# MCP39F511A.net
KiCad netlist of a schematic drawn in Altium Designer
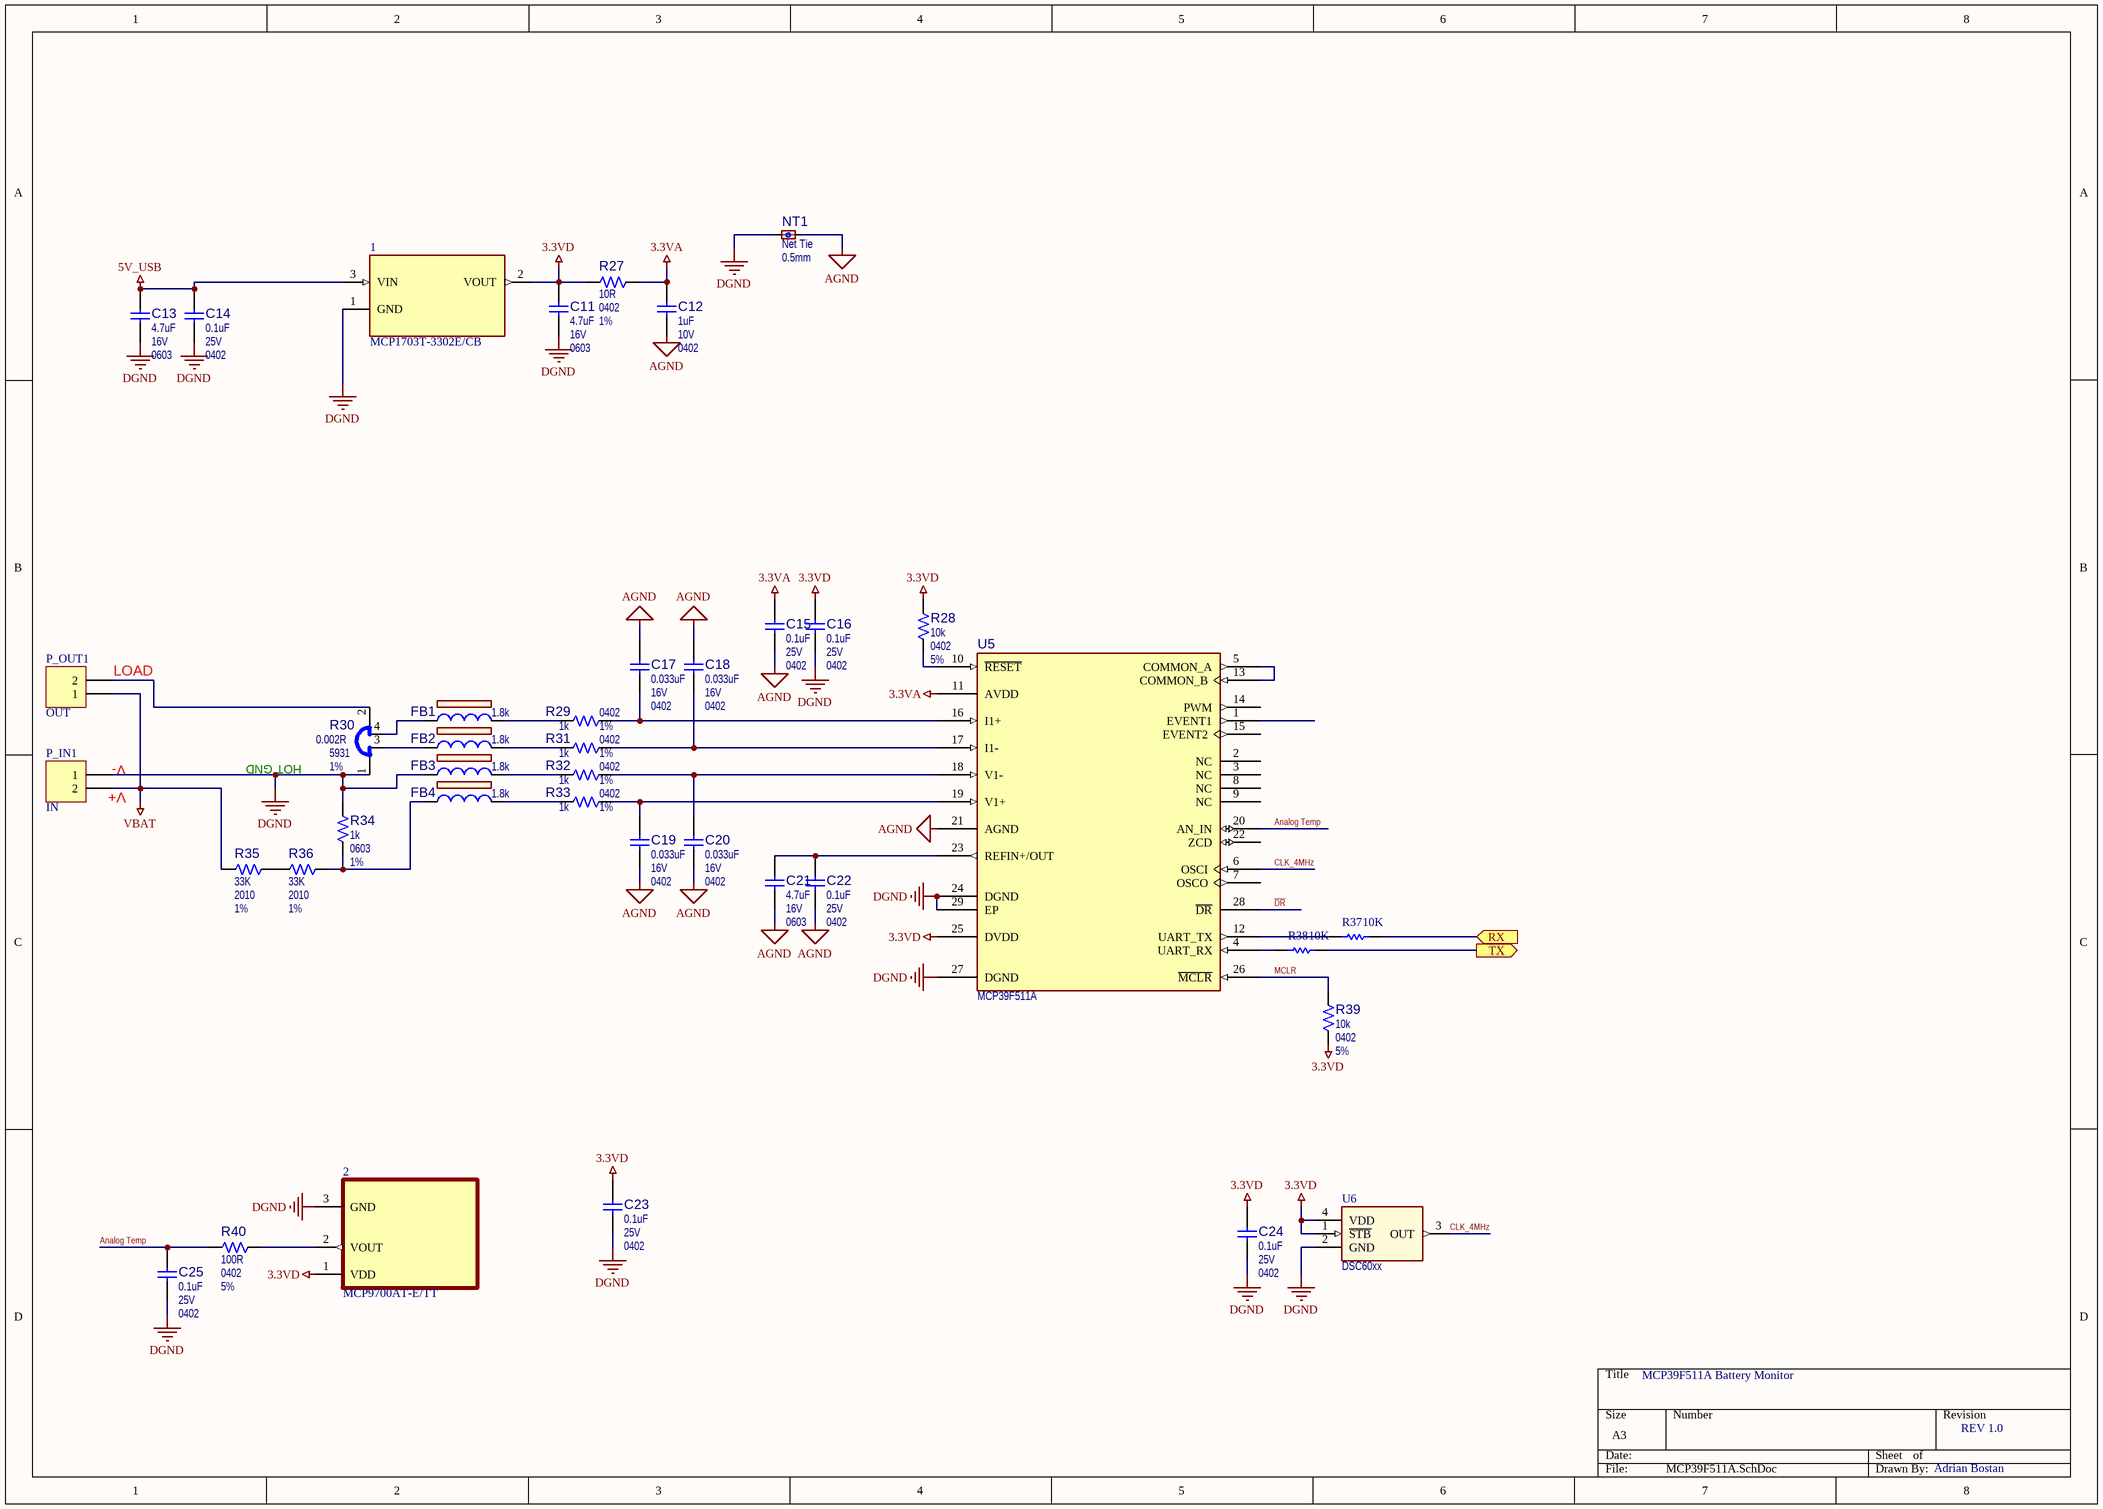
[diagram p0: MCP39F511A.SchDoc]

(export (version "E")
  (design (tool "Eeschema 10.0.6"))
  (components
    (comp (ref "1")
      (value "MCP1703T-3302E/CB")
      (footprint "SOT95P300X145-3N")
      (description "Linear Voltage Regulator IC 1 Output 250mA SOT-23A-3")
      (fields (field (name "MF") "Microchip"))
      (libsource (lib "MCP1703T-3302E_CB") (part "MCP1703T-3302E/CB"))
    )
    (comp (ref "2")
      (value "MCP9700AT-E/TT")
      (footprint "SOT95P237X112-3N")
      (description "Temperature Sensor Analog, Local -40Â°C ~ 125Â°C 10mV/Â°C SOT-23-3")
      (fields (field (name "MF") "Microchip"))
      (libsource (lib "MCP9700AT-E_TT") (part "MCP9700AT-E/TT"))
    )
    (comp (ref "C11")
      (value "4.7uF")
      (footprint "CAP0603M")
      (description "Capacitor")
      (fields
        (field (name "VOLTAGE") "16V")
        (field (name "PACKAGE") "0603")
        (field (name "TOLERANCE") "10%")
        (field (name "OWNER") "Jairuz Agang-ang")
      )
      (libsource (lib "MCHP-CDB") (part "Capacitor NP"))
    )
    (comp (ref "C12")
      (value "1uF")
      (footprint "CAP0603M")
      (description "Capacitor")
      (fields
        (field (name "VOLTAGE") "10V")
        (field (name "PACKAGE") "0402")
        (field (name "TOLERANCE") "10%")
        (field (name "OWNER") "Aaron VanDuerm")
      )
      (libsource (lib "MCHP-CDB") (part "Capacitor NP"))
    )
    (comp (ref "C13")
      (value "4.7uF")
      (footprint "CAP0603M")
      (description "Capacitor")
      (fields
        (field (name "VOLTAGE") "16V")
        (field (name "PACKAGE") "0603")
        (field (name "TOLERANCE") "10%")
        (field (name "OWNER") "Jairuz Agang-ang")
      )
      (libsource (lib "MCHP-CDB") (part "Capacitor NP"))
    )
    (comp (ref "C14")
      (value "0.1uF")
      (footprint "CAP0603M")
      (description "Capacitor")
      (fields
        (field (name "VOLTAGE") "25V")
        (field (name "PACKAGE") "0402")
        (field (name "TOLERANCE") "10%")
        (field (name "OWNER") "Randolph Sobrepena")
      )
      (libsource (lib "MCHP-CDB") (part "Capacitor NP"))
    )
    (comp (ref "C15")
      (value "0.1uF")
      (footprint "CAP0603M")
      (description "Capacitor")
      (fields
        (field (name "VOLTAGE") "25V")
        (field (name "PACKAGE") "0402")
        (field (name "TOLERANCE") "10%")
        (field (name "OWNER") "Randolph Sobrepena")
      )
      (libsource (lib "MCHP-CDB") (part "Capacitor NP"))
    )
    (comp (ref "C16")
      (value "0.1uF")
      (footprint "CAP0603M")
      (description "Capacitor")
      (fields
        (field (name "VOLTAGE") "25V")
        (field (name "PACKAGE") "0402")
        (field (name "TOLERANCE") "10%")
        (field (name "OWNER") "Randolph Sobrepena")
      )
      (libsource (lib "MCHP-CDB") (part "Capacitor NP"))
    )
    (comp (ref "C17")
      (value "0.033uF")
      (footprint "CAP0603M")
      (description "Capacitor")
      (fields
        (field (name "VOLTAGE") "16V")
        (field (name "PACKAGE") "0402")
        (field (name "TOLERANCE") "10%")
        (field (name "OWNER") "Bogdan Popescu")
      )
      (libsource (lib "MCHP-CDB") (part "Capacitor NP"))
    )
    (comp (ref "C18")
      (value "0.033uF")
      (footprint "CAP0603M")
      (description "Capacitor")
      (fields
        (field (name "VOLTAGE") "16V")
        (field (name "PACKAGE") "0402")
        (field (name "TOLERANCE") "10%")
        (field (name "OWNER") "Bogdan Popescu")
      )
      (libsource (lib "MCHP-CDB") (part "Capacitor NP"))
    )
    (comp (ref "C19")
      (value "0.033uF")
      (footprint "CAP0603M")
      (description "Capacitor")
      (fields
        (field (name "VOLTAGE") "16V")
        (field (name "PACKAGE") "0402")
        (field (name "TOLERANCE") "10%")
        (field (name "OWNER") "Bogdan Popescu")
      )
      (libsource (lib "MCHP-CDB") (part "Capacitor NP"))
    )
    (comp (ref "C20")
      (value "0.033uF")
      (footprint "CAP0603M")
      (description "Capacitor")
      (fields
        (field (name "VOLTAGE") "16V")
        (field (name "PACKAGE") "0402")
        (field (name "TOLERANCE") "10%")
        (field (name "OWNER") "Bogdan Popescu")
      )
      (libsource (lib "MCHP-CDB") (part "Capacitor NP"))
    )
    (comp (ref "C21")
      (value "4.7uF")
      (footprint "CAP0603M")
      (description "Capacitor")
      (fields
        (field (name "VOLTAGE") "16V")
        (field (name "PACKAGE") "0603")
        (field (name "TOLERANCE") "10%")
        (field (name "OWNER") "Jairuz Agang-ang")
      )
      (libsource (lib "MCHP-CDB") (part "Capacitor NP"))
    )
    (comp (ref "C22")
      (value "0.1uF")
      (footprint "CAP0603M")
      (description "Capacitor")
      (fields
        (field (name "VOLTAGE") "25V")
        (field (name "PACKAGE") "0402")
        (field (name "TOLERANCE") "10%")
        (field (name "OWNER") "Randolph Sobrepena")
      )
      (libsource (lib "MCHP-CDB") (part "Capacitor NP"))
    )
    (comp (ref "C23")
      (value "0.1uF")
      (footprint "CAP0603M")
      (description "Capacitor")
      (fields
        (field (name "VOLTAGE") "25V")
        (field (name "PACKAGE") "0402")
        (field (name "TOLERANCE") "10%")
        (field (name "OWNER") "Randolph Sobrepena")
      )
      (libsource (lib "MCHP-CDB") (part "Capacitor NP"))
    )
    (comp (ref "C24")
      (value "0.1uF")
      (footprint "CAP0603M")
      (description "Capacitor")
      (fields
        (field (name "VOLTAGE") "25V")
        (field (name "PACKAGE") "0402")
        (field (name "TOLERANCE") "10%")
        (field (name "OWNER") "Randolph Sobrepena")
      )
      (libsource (lib "MCHP-CDB") (part "Capacitor NP"))
    )
    (comp (ref "C25")
      (value "0.1uF")
      (footprint "CAP0603M")
      (description "Capacitor")
      (fields
        (field (name "VOLTAGE") "25V")
        (field (name "PACKAGE") "0402")
        (field (name "TOLERANCE") "10%")
        (field (name "OWNER") "Randolph Sobrepena")
      )
      (libsource (lib "MCHP-CDB") (part "Capacitor NP"))
    )
    (comp (ref "FB1")
      (value "1.8k")
      (footprint "RES0603M")
      (fields (field (name "OWNER") "Razvan Cristescu"))
      (libsource (lib "MCHP-CDB") (part "Ferrite Bead"))
    )
    (comp (ref "FB2")
      (value "1.8k")
      (footprint "RES0603M")
      (fields (field (name "OWNER") "Razvan Cristescu"))
      (libsource (lib "MCHP-CDB") (part "Ferrite Bead"))
    )
    (comp (ref "FB3")
      (value "1.8k")
      (footprint "RES0603M")
      (fields (field (name "OWNER") "Razvan Cristescu"))
      (libsource (lib "MCHP-CDB") (part "Ferrite Bead"))
    )
    (comp (ref "FB4")
      (value "1.8k")
      (footprint "RES0603M")
      (fields (field (name "OWNER") "Razvan Cristescu"))
      (libsource (lib "MCHP-CDB") (part "Ferrite Bead"))
    )
    (comp (ref "NT1")
      (value "Net Tie")
      (footprint "NET_TIE_0.5mm")
      (fields (field (name "PACKAGE") "0.5mm") (field (name "OWNER") "Bogdan P (M91398)"))
      (libsource (lib "MCHP-CDB") (part "Net Tie"))
    )
    (comp (ref "P_IN1")
      (value "IN")
      (footprint "XT60PW-M")
      (description "Header, 2-Pin")
      (fields (field (name "PUBLISHER") "Altium Limited"))
      (libsource (lib "Miscellaneous Connectors") (part "Header 2"))
    )
    (comp (ref "P_OUT1")
      (value "OUT")
      (footprint "XT60PW-F")
      (description "Header, 2-Pin")
      (fields (field (name "PUBLISHER") "Altium Limited"))
      (libsource (lib "") (part "Header 2_1"))
    )
    (comp (ref "R27")
      (value "10R")
      (footprint "RES0603M")
      (description "Resistor")
      (fields
        (field (name "PACKAGE") "0402")
        (field (name "TOLERANCE") "1%")
        (field (name "VOLTAGE") "50V")
        (field (name "POWER") "1/16W")
        (field (name "OWNER") "Tad Ahlvers")
      )
      (libsource (lib "MCHP-CDB") (part "Resistor"))
    )
    (comp (ref "R28")
      (value "10k")
      (footprint "RES0603M")
      (description "Resistor")
      (fields
        (field (name "PACKAGE") "0402")
        (field (name "TOLERANCE") "5%")
        (field (name "VOLTAGE") "50V")
        (field (name "POWER") "1/16W")
      )
      (libsource (lib "MCHP-CDB") (part "Resistor"))
    )
    (comp (ref "R29")
      (value "1k")
      (footprint "RES0603M")
      (description "Resistor")
      (fields
        (field (name "PACKAGE") "0402")
        (field (name "TOLERANCE") "1%")
        (field (name "VOLTAGE") "50V")
        (field (name "POWER") "1/10W")
        (field (name "OWNER") "Tad Ahlvers")
      )
      (libsource (lib "MCHP-CDB") (part "Resistor"))
    )
    (comp (ref "R30")
      (value "0.002R")
      (footprint "5931")
      (description "Shunt")
      (fields
        (field (name "PACKAGE") "5931")
        (field (name "TOLERANCE") "1%")
        (field (name "VOLTAGE") "200V")
        (field (name "POWER") "2W")
        (field (name "OWNER") "Bogdan P (M91398)")
      )
      (libsource (lib "MCHP-CDB") (part "Shunt 4 Pin"))
    )
    (comp (ref "R31")
      (value "1k")
      (footprint "RES0603M")
      (description "Resistor")
      (fields
        (field (name "PACKAGE") "0402")
        (field (name "TOLERANCE") "1%")
        (field (name "VOLTAGE") "50V")
        (field (name "POWER") "1/10W")
        (field (name "OWNER") "Tad Ahlvers")
      )
      (libsource (lib "MCHP-CDB") (part "Resistor"))
    )
    (comp (ref "R32")
      (value "1k")
      (footprint "RES0603M")
      (description "Resistor")
      (fields
        (field (name "PACKAGE") "0402")
        (field (name "TOLERANCE") "1%")
        (field (name "VOLTAGE") "50V")
        (field (name "POWER") "1/10W")
        (field (name "OWNER") "Tad Ahlvers")
      )
      (libsource (lib "MCHP-CDB") (part "Resistor"))
    )
    (comp (ref "R33")
      (value "1k")
      (footprint "RES0603M")
      (description "Resistor")
      (fields
        (field (name "PACKAGE") "0402")
        (field (name "TOLERANCE") "1%")
        (field (name "VOLTAGE") "50V")
        (field (name "POWER") "1/10W")
        (field (name "OWNER") "Tad Ahlvers")
      )
      (libsource (lib "MCHP-CDB") (part "Resistor"))
    )
    (comp (ref "R34")
      (value "1k")
      (footprint "RES0603M")
      (description "Resistor")
      (fields
        (field (name "PACKAGE") "0603")
        (field (name "TOLERANCE") "1%")
        (field (name "VOLTAGE") "75V")
        (field (name "POWER") "1/10W")
      )
      (libsource (lib "MCHP-CDB") (part "Resistor"))
    )
    (comp (ref "R35")
      (value "33K")
      (footprint "RES2010")
      (description "Resistor")
      (fields
        (field (name "PACKAGE") "2010")
        (field (name "TOLERANCE") "1%")
        (field (name "VOLTAGE") "400V")
        (field (name "POWER") "3/4W")
        (field (name "OWNER") "Bogdan Popescu")
      )
      (libsource (lib "MCHP-CDB") (part "Resistor"))
    )
    (comp (ref "R36")
      (value "33K")
      (footprint "RES2010")
      (description "Resistor")
      (fields
        (field (name "PACKAGE") "2010")
        (field (name "TOLERANCE") "1%")
        (field (name "VOLTAGE") "400V")
        (field (name "POWER") "3/4W")
        (field (name "OWNER") "Bogdan Popescu")
      )
      (libsource (lib "MCHP-CDB") (part "Resistor"))
    )
    (comp (ref "R37")
      (value "10K")
      (footprint "RES0603M")
      (description "Resistor")
      (fields (field (name "Comment") "Res1") (field (name "PUBLISHER") "Altium Limited"))
      (libsource (lib "Miscellaneous Devices") (part "Res1"))
    )
    (comp (ref "R38")
      (value "10K")
      (footprint "RES0603M")
      (description "Resistor")
      (fields (field (name "Comment") "Res1") (field (name "PUBLISHER") "Altium Limited"))
      (libsource (lib "Miscellaneous Devices") (part "Res1"))
    )
    (comp (ref "R39")
      (value "10k")
      (footprint "RES0603M")
      (description "Resistor")
      (fields
        (field (name "PACKAGE") "0402")
        (field (name "TOLERANCE") "5%")
        (field (name "VOLTAGE") "50V")
        (field (name "POWER") "1/16W")
      )
      (libsource (lib "MCHP-CDB") (part "Resistor"))
    )
    (comp (ref "R40")
      (value "100R")
      (footprint "RES0603M")
      (description "Resistor")
      (fields
        (field (name "PACKAGE") "0402")
        (field (name "TOLERANCE") "5%")
        (field (name "VOLTAGE") "50V")
        (field (name "POWER") "1/16W")
        (field (name "OWNER") "Sompoch Loboonlert")
      )
      (libsource (lib "MCHP-CDB") (part "Resistor"))
    )
    (comp (ref "U5")
      (value "MCP39F511A")
      (footprint "QFN50P500X500X100-29N")
      (description "ADC")
      (fields (field (name "Comment") "MCP39F511 QFN-28") (field (name "OWNER") "Bogdan Popescu"))
      (libsource (lib "MCHP-CDB") (part "MCP39F511 QFN-28"))
    )
    (comp (ref "U6")
      (value "DSC60xx")
      (footprint "DSC60xx")
      (fields (field (name "Comment") "OSCILLATOR DSC1001") (field (name "OWNER") "Tim Moffat"))
      (libsource (lib "MCHP-CDB") (part "OSCILLATOR DSC1001"))
    )
  )
  (nets
    (net (code "1") (name "/Analog Temp") (class "Default")
      (node (ref "C25") (pin "2") (pinfunction "2_2") (pintype "passive"))
      (node (ref "R40") (pin "1") (pinfunction "1_1") (pintype "passive"))
      (node (ref "U5") (pin "20") (pinfunction "AN_IN_20") (pintype "bidirectional"))
    )
    (net (code "2") (name "/CLK_4MHz") (class "Default")
      (node (ref "U5") (pin "6") (pinfunction "OSCI_6") (pintype "input"))
      (node (ref "U6") (pin "3") (pinfunction "OUT_3") (pintype "output"))
    )
    (net (code "3") (name "/MCLR") (class "Default")
      (node (ref "R39") (pin "2") (pinfunction "2_2") (pintype "passive"))
      (node (ref "U5") (pin "26") (pinfunction "~{MCLR}_26") (pintype "input"))
    )
    (net (code "4") (name "/RX") (class "Default")
      (node (ref "R37") (pin "1") (pinfunction "1_1") (pintype "passive"))
    )
    (net (code "5") (name "/TX") (class "Default")
      (node (ref "R38") (pin "1") (pinfunction "1_1") (pintype "passive"))
    )
    (net (code "6") (name "/~{DR}") (class "Default")
      (node (ref "U5") (pin "28") (pinfunction "~{DR}_28") (pintype "tri_state"))
    )
    (net (code "7") (name "3.3VA") (class "Default")
      (node (ref "C12") (pin "2") (pinfunction "2_2") (pintype "passive"))
      (node (ref "C15") (pin "2") (pinfunction "2_2") (pintype "passive"))
      (node (ref "R27") (pin "2") (pinfunction "2_2") (pintype "passive"))
      (node (ref "U5") (pin "11") (pinfunction "AVDD_11") (pintype "power_in"))
    )
    (net (code "8") (name "3.3VD") (class "Default")
      (node (ref "1") (pin "2") (pinfunction "VOUT_2") (pintype "output"))
      (node (ref "2") (pin "1") (pinfunction "VDD_1") (pintype "power_in"))
      (node (ref "C11") (pin "2") (pinfunction "2_2") (pintype "passive"))
      (node (ref "C16") (pin "2") (pinfunction "2_2") (pintype "passive"))
      (node (ref "C23") (pin "2") (pinfunction "2_2") (pintype "passive"))
      (node (ref "C24") (pin "2") (pinfunction "2_2") (pintype "passive"))
      (node (ref "R27") (pin "1") (pinfunction "1_1") (pintype "passive"))
      (node (ref "R28") (pin "2") (pinfunction "2_2") (pintype "passive"))
      (node (ref "R39") (pin "1") (pinfunction "1_1") (pintype "passive"))
      (node (ref "U5") (pin "25") (pinfunction "DVDD_25") (pintype "power_in"))
      (node (ref "U6") (pin "1") (pinfunction "~{STB}_1") (pintype "input"))
      (node (ref "U6") (pin "4") (pinfunction "VDD_4") (pintype "power_in"))
    )
    (net (code "9") (name "5V_USB") (class "Default")
      (node (ref "1") (pin "3") (pinfunction "VIN_3") (pintype "input"))
      (node (ref "C13") (pin "1") (pinfunction "1_1") (pintype "passive"))
      (node (ref "C14") (pin "2") (pinfunction "2_2") (pintype "passive"))
    )
    (net (code "10") (name "AGND") (class "Default")
      (node (ref "C12") (pin "1") (pinfunction "1_1") (pintype "passive"))
      (node (ref "C15") (pin "1") (pinfunction "1_1") (pintype "passive"))
      (node (ref "C17") (pin "2") (pinfunction "2_2") (pintype "passive"))
      (node (ref "C18") (pin "2") (pinfunction "2_2") (pintype "passive"))
      (node (ref "C19") (pin "1") (pinfunction "1_1") (pintype "passive"))
      (node (ref "C20") (pin "1") (pinfunction "1_1") (pintype "passive"))
      (node (ref "C21") (pin "1") (pinfunction "1_1") (pintype "passive"))
      (node (ref "C22") (pin "1") (pinfunction "1_1") (pintype "passive"))
      (node (ref "NT1") (pin "2") (pinfunction "2_2") (pintype "passive"))
      (node (ref "U5") (pin "21") (pinfunction "AGND_21") (pintype "power_in"))
    )
    (net (code "11") (name "DGND") (class "Default")
      (node (ref "1") (pin "1") (pinfunction "GND_1") (pintype "passive"))
      (node (ref "2") (pin "3") (pinfunction "GND_3") (pintype "power_in"))
      (node (ref "C11") (pin "1") (pinfunction "1_1") (pintype "passive"))
      (node (ref "C13") (pin "2") (pinfunction "2_2") (pintype "passive"))
      (node (ref "C14") (pin "1") (pinfunction "1_1") (pintype "passive"))
      (node (ref "C16") (pin "1") (pinfunction "1_1") (pintype "passive"))
      (node (ref "C23") (pin "1") (pinfunction "1_1") (pintype "passive"))
      (node (ref "C24") (pin "1") (pinfunction "1_1") (pintype "passive"))
      (node (ref "C25") (pin "1") (pinfunction "1_1") (pintype "passive"))
      (node (ref "FB3") (pin "1") (pinfunction "1_1") (pintype "passive"))
      (node (ref "NT1") (pin "1") (pinfunction "1_1") (pintype "passive"))
      (node (ref "P_IN1") (pin "1") (pinfunction "1_1") (pintype "passive"))
      (node (ref "R30") (pin "1") (pinfunction "1_1") (pintype "passive"))
      (node (ref "R34") (pin "2") (pinfunction "2_2") (pintype "passive"))
      (node (ref "U5") (pin "24") (pinfunction "DGND_24") (pintype "power_in"))
      (node (ref "U5") (pin "27") (pinfunction "DGND_27") (pintype "power_in"))
      (node (ref "U5") (pin "29") (pinfunction "EP_29") (pintype "passive"))
      (node (ref "U6") (pin "2") (pinfunction "GND_2") (pintype "power_in"))
    )
    (net (code "12") (name "Net-(2-VOUT)") (class "Default")
      (node (ref "2") (pin "2") (pinfunction "VOUT_2") (pintype "output"))
      (node (ref "R40") (pin "2") (pinfunction "2_2") (pintype "passive"))
    )
    (net (code "13") (name "Net-(FB1-Pad1)") (class "Default")
      (node (ref "FB1") (pin "1") (pinfunction "1_1") (pintype "passive"))
      (node (ref "R30") (pin "4") (pinfunction "4_4") (pintype "passive"))
    )
    (net (code "14") (name "Net-(FB1-Pad2)") (class "Default")
      (node (ref "FB1") (pin "2") (pinfunction "2_2") (pintype "passive"))
      (node (ref "R29") (pin "1") (pinfunction "1_1") (pintype "passive"))
    )
    (net (code "15") (name "Net-(FB2-Pad1)") (class "Default")
      (node (ref "FB2") (pin "1") (pinfunction "1_1") (pintype "passive"))
      (node (ref "R30") (pin "3") (pinfunction "3_3") (pintype "passive"))
    )
    (net (code "16") (name "Net-(FB2-Pad2)") (class "Default")
      (node (ref "FB2") (pin "2") (pinfunction "2_2") (pintype "passive"))
      (node (ref "R31") (pin "1") (pinfunction "1_1") (pintype "passive"))
    )
    (net (code "17") (name "Net-(FB3-Pad2)") (class "Default")
      (node (ref "FB3") (pin "2") (pinfunction "2_2") (pintype "passive"))
      (node (ref "R32") (pin "1") (pinfunction "1_1") (pintype "passive"))
    )
    (net (code "18") (name "Net-(FB4-Pad1)") (class "Default")
      (node (ref "FB4") (pin "1") (pinfunction "1_1") (pintype "passive"))
      (node (ref "R34") (pin "1") (pinfunction "1_1") (pintype "passive"))
      (node (ref "R36") (pin "1") (pinfunction "1_1") (pintype "passive"))
    )
    (net (code "19") (name "Net-(FB4-Pad2)") (class "Default")
      (node (ref "FB4") (pin "2") (pinfunction "2_2") (pintype "passive"))
      (node (ref "R33") (pin "1") (pinfunction "1_1") (pintype "passive"))
    )
    (net (code "20") (name "Net-(P_OUT1-Pad2)") (class "Default")
      (node (ref "P_OUT1") (pin "2") (pinfunction "2_2") (pintype "passive"))
      (node (ref "R30") (pin "2") (pinfunction "2_2") (pintype "passive"))
    )
    (net (code "21") (name "Net-(R35-Pad2)") (class "Default")
      (node (ref "R35") (pin "2") (pinfunction "2_2") (pintype "passive"))
      (node (ref "R36") (pin "2") (pinfunction "2_2") (pintype "passive"))
    )
    (net (code "22") (name "Net-(U5-COMMON_A)") (class "Default")
      (node (ref "U5") (pin "13") (pinfunction "COMMON_B_13") (pintype "input"))
      (node (ref "U5") (pin "5") (pinfunction "COMMON_A_5") (pintype "output"))
    )
    (net (code "23") (name "Net-(U5-I1+)") (class "Default")
      (node (ref "C17") (pin "1") (pinfunction "1_1") (pintype "passive"))
      (node (ref "R29") (pin "2") (pinfunction "2_2") (pintype "passive"))
      (node (ref "U5") (pin "16") (pinfunction "I1+_16") (pintype "input"))
    )
    (net (code "24") (name "Net-(U5-I1-)") (class "Default")
      (node (ref "C18") (pin "1") (pinfunction "1_1") (pintype "passive"))
      (node (ref "R31") (pin "2") (pinfunction "2_2") (pintype "passive"))
      (node (ref "U5") (pin "17") (pinfunction "I1-_17") (pintype "input"))
    )
    (net (code "25") (name "Net-(U5-REFIN+{slash}OUT)") (class "Default")
      (node (ref "C21") (pin "2") (pinfunction "2_2") (pintype "passive"))
      (node (ref "C22") (pin "2") (pinfunction "2_2") (pintype "passive"))
      (node (ref "U5") (pin "23") (pinfunction "REFIN+/OUT_23") (pintype "output"))
    )
    (net (code "26") (name "Net-(U5-UART_RX)") (class "Default")
      (node (ref "R38") (pin "2") (pinfunction "2_2") (pintype "passive"))
      (node (ref "U5") (pin "4") (pinfunction "UART_RX_4") (pintype "input"))
    )
    (net (code "27") (name "Net-(U5-UART_TX)") (class "Default")
      (node (ref "R37") (pin "2") (pinfunction "2_2") (pintype "passive"))
      (node (ref "U5") (pin "12") (pinfunction "UART_TX_12") (pintype "output"))
    )
    (net (code "28") (name "Net-(U5-V1+)") (class "Default")
      (node (ref "C19") (pin "2") (pinfunction "2_2") (pintype "passive"))
      (node (ref "R33") (pin "2") (pinfunction "2_2") (pintype "passive"))
      (node (ref "U5") (pin "19") (pinfunction "V1+_19") (pintype "input"))
    )
    (net (code "29") (name "Net-(U5-V1-)") (class "Default")
      (node (ref "C20") (pin "2") (pinfunction "2_2") (pintype "passive"))
      (node (ref "R32") (pin "2") (pinfunction "2_2") (pintype "passive"))
      (node (ref "U5") (pin "18") (pinfunction "V1-_18") (pintype "input"))
    )
    (net (code "30") (name "Net-(U5-~{RESET})") (class "Default")
      (node (ref "R28") (pin "1") (pinfunction "1_1") (pintype "passive"))
      (node (ref "U5") (pin "10") (pinfunction "~{RESET}_10") (pintype "input"))
    )
    (net (code "31") (name "VBAT") (class "Default")
      (node (ref "P_IN1") (pin "2") (pinfunction "2_2") (pintype "passive"))
      (node (ref "P_OUT1") (pin "1") (pinfunction "1_1") (pintype "passive"))
      (node (ref "R35") (pin "1") (pinfunction "1_1") (pintype "passive"))
    )
    (net (code "32") (name "unconnected-(U5-EVENT1-Pad1)") (class "Default")
      (node (ref "U5") (pin "1") (pinfunction "EVENT1_1") (pintype "output"))
    )
    (net (code "33") (name "unconnected-(U5-EVENT2-Pad15)") (class "Default")
      (node (ref "U5") (pin "15") (pinfunction "EVENT2_15") (pintype "output"))
    )
    (net (code "34") (name "unconnected-(U5-NC-Pad2)") (class "Default")
      (node (ref "U5") (pin "2") (pinfunction "NC_2") (pintype "tri_state"))
    )
    (net (code "35") (name "unconnected-(U5-NC-Pad3)") (class "Default")
      (node (ref "U5") (pin "3") (pinfunction "NC_3") (pintype "tri_state"))
    )
    (net (code "36") (name "unconnected-(U5-NC-Pad8)") (class "Default")
      (node (ref "U5") (pin "8") (pinfunction "NC_8") (pintype "tri_state"))
    )
    (net (code "37") (name "unconnected-(U5-NC-Pad9)") (class "Default")
      (node (ref "U5") (pin "9") (pinfunction "NC_9") (pintype "tri_state"))
    )
    (net (code "38") (name "unconnected-(U5-OSCO-Pad7)") (class "Default")
      (node (ref "U5") (pin "7") (pinfunction "OSCO_7") (pintype "output"))
    )
    (net (code "39") (name "unconnected-(U5-PWM-Pad14)") (class "Default")
      (node (ref "U5") (pin "14") (pinfunction "PWM_14") (pintype "output"))
    )
    (net (code "40") (name "unconnected-(U5-ZCD-Pad22)") (class "Default")
      (node (ref "U5") (pin "22") (pinfunction "ZCD_22") (pintype "bidirectional"))
    )
  )
)
